# FRDM-Robot-Rev1_9.net
KiCad netlist of a schematic drawn in EAGLE
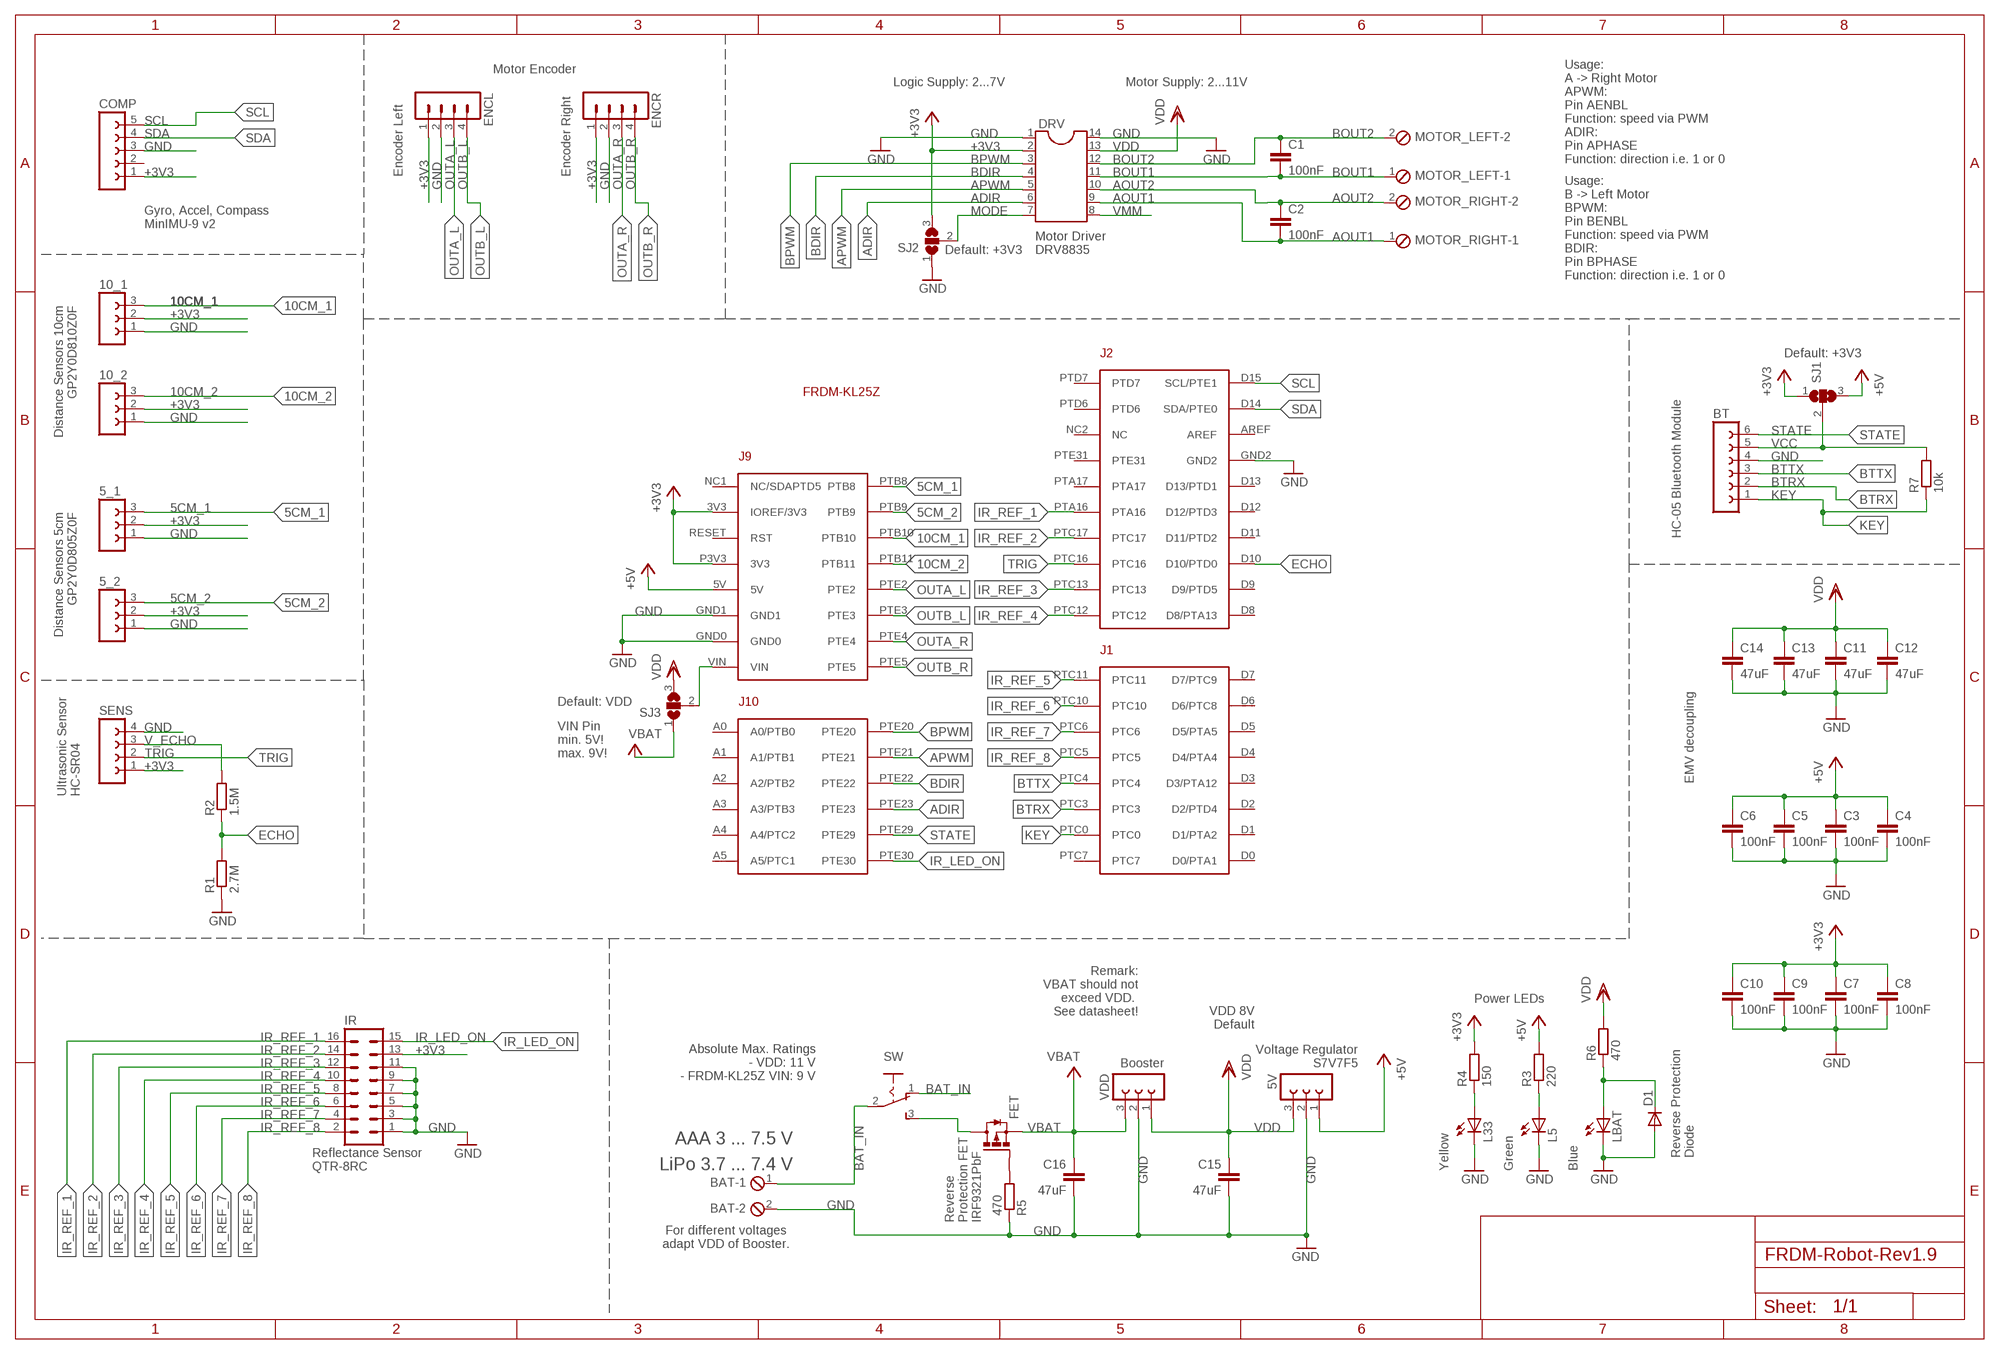
[diagram p0: schematic, sheet 1]

(export (version "E")
  (design (tool "Eeschema 10.0.6"))
  (components
    (comp (ref "5V")
      (value "FE03-1")
      (footprint "eagle-import:FE03-1")
      (libsource (lib "eagle-import") (part "FE03-1"))
    )
    (comp (ref "5_1")
      (value "FE03-1")
      (footprint "eagle-import:FE03-1")
      (libsource (lib "eagle-import") (part "FE03-1"))
    )
    (comp (ref "5_2")
      (value "FE03-1")
      (footprint "eagle-import:FE03-1")
      (libsource (lib "eagle-import") (part "FE03-1"))
    )
    (comp (ref "10_1")
      (value "FE03-1")
      (footprint "eagle-import:FE03-1")
      (libsource (lib "eagle-import") (part "FE03-1"))
    )
    (comp (ref "10_2")
      (value "FE03-1")
      (footprint "eagle-import:FE03-1")
      (libsource (lib "eagle-import") (part "FE03-1"))
    )
    (comp (ref "BAT")
      (value "MPT2")
      (footprint "eagle-import:2POL254")
      (libsource (lib "eagle-import") (part "MPT2"))
    )
    (comp (ref "BT")
      (value "FE06-1")
      (footprint "eagle-import:FE06")
      (libsource (lib "eagle-import") (part "FE06-1"))
    )
    (comp (ref "C1")
      (value "100nF")
      (footprint "eagle-import:C0805")
      (libsource (lib "eagle-import") (part "C-EUC0805"))
    )
    (comp (ref "C2")
      (value "100nF")
      (footprint "eagle-import:C0805")
      (libsource (lib "eagle-import") (part "C-EUC0805"))
    )
    (comp (ref "C3")
      (value "100nF")
      (footprint "eagle-import:C0805")
      (libsource (lib "eagle-import") (part "C-EUC0805"))
    )
    (comp (ref "C4")
      (value "100nF")
      (footprint "eagle-import:C0805")
      (libsource (lib "eagle-import") (part "C-EUC0805"))
    )
    (comp (ref "C5")
      (value "100nF")
      (footprint "eagle-import:C0805")
      (libsource (lib "eagle-import") (part "C-EUC0805"))
    )
    (comp (ref "C6")
      (value "100nF")
      (footprint "eagle-import:C0805")
      (libsource (lib "eagle-import") (part "C-EUC0805"))
    )
    (comp (ref "C7")
      (value "100nF")
      (footprint "eagle-import:C0805")
      (libsource (lib "eagle-import") (part "C-EUC0805"))
    )
    (comp (ref "C8")
      (value "100nF")
      (footprint "eagle-import:C0805")
      (libsource (lib "eagle-import") (part "C-EUC0805"))
    )
    (comp (ref "C9")
      (value "100nF")
      (footprint "eagle-import:C0805")
      (libsource (lib "eagle-import") (part "C-EUC0805"))
    )
    (comp (ref "C10")
      (value "100nF")
      (footprint "eagle-import:C0805")
      (libsource (lib "eagle-import") (part "C-EUC0805"))
    )
    (comp (ref "C11")
      (value "47uF")
      (footprint "eagle-import:C0805")
      (libsource (lib "eagle-import") (part "C-EUC0805"))
    )
    (comp (ref "C12")
      (value "47uF")
      (footprint "eagle-import:C0805")
      (libsource (lib "eagle-import") (part "C-EUC0805"))
    )
    (comp (ref "C13")
      (value "47uF")
      (footprint "eagle-import:C0805")
      (libsource (lib "eagle-import") (part "C-EUC0805"))
    )
    (comp (ref "C14")
      (value "47uF")
      (footprint "eagle-import:C0805")
      (libsource (lib "eagle-import") (part "C-EUC0805"))
    )
    (comp (ref "C15")
      (value "47uF")
      (footprint "eagle-import:C0805")
      (libsource (lib "eagle-import") (part "C-EUC0805"))
    )
    (comp (ref "C16")
      (value "47uF")
      (footprint "eagle-import:C0805")
      (libsource (lib "eagle-import") (part "C-EUC0805"))
    )
    (comp (ref "COMP")
      (value "FE05-1")
      (footprint "eagle-import:FE05-1")
      (libsource (lib "eagle-import") (part "FE05-1"))
    )
    (comp (ref "D1")
      (value "DIODE-SOD123")
      (footprint "eagle-import:SOD123")
      (libsource (lib "eagle-import") (part "DIODE-SOD123"))
    )
    (comp (ref "DRV")
      (value "DIL14")
      (footprint "eagle-import:DIL14")
      (libsource (lib "eagle-import") (part "DIL14"))
    )
    (comp (ref "ENCL")
      (value "MA04-1")
      (footprint "eagle-import:MA04-1")
      (libsource (lib "eagle-import") (part "MA04-1"))
    )
    (comp (ref "ENCR")
      (value "MA04-1")
      (footprint "eagle-import:MA04-1")
      (libsource (lib "eagle-import") (part "MA04-1"))
    )
    (comp (ref "FET")
      (value "P-MOSFET-SO8")
      (footprint "eagle-import:SO-08")
      (libsource (lib "eagle-import") (part "P-MOSFET-SO8"))
    )
    (comp (ref "FRDM1")
      (value "FRDM-KL25ZARDUINO")
      (footprint "eagle-import:FRDM-KL25Z")
      (libsource (lib "eagle-import") (part "FRDM-KL25ZARDUINO"))
    )
    (comp (ref "IR")
      (value "MA08-2")
      (footprint "eagle-import:MA08-2")
      (libsource (lib "eagle-import") (part "MA08-2"))
    )
    (comp (ref "L5")
      (value "LEDCHIP-LED0603")
      (footprint "eagle-import:CHIP-LED0603")
      (libsource (lib "eagle-import") (part "LEDCHIP-LED0603"))
    )
    (comp (ref "L33")
      (value "LEDCHIP-LED0603")
      (footprint "eagle-import:CHIP-LED0603")
      (libsource (lib "eagle-import") (part "LEDCHIP-LED0603"))
    )
    (comp (ref "LBAT")
      (value "LEDCHIP-LED0603")
      (footprint "eagle-import:CHIP-LED0603")
      (libsource (lib "eagle-import") (part "LEDCHIP-LED0603"))
    )
    (comp (ref "MOTOR_LEFT")
      (value "MPT2")
      (footprint "eagle-import:2POL254")
      (libsource (lib "eagle-import") (part "MPT2"))
    )
    (comp (ref "MOTOR_RIGHT")
      (value "MPT2")
      (footprint "eagle-import:2POL254")
      (libsource (lib "eagle-import") (part "MPT2"))
    )
    (comp (ref "R1")
      (value "2.7M")
      (footprint "eagle-import:M0805")
      (libsource (lib "eagle-import") (part "R-EU_M0805"))
    )
    (comp (ref "R2")
      (value "1.5M")
      (footprint "eagle-import:M0805")
      (libsource (lib "eagle-import") (part "R-EU_M0805"))
    )
    (comp (ref "R3")
      (value "220")
      (footprint "eagle-import:M0805")
      (libsource (lib "eagle-import") (part "R-EU_M0805"))
    )
    (comp (ref "R4")
      (value "150")
      (footprint "eagle-import:M0805")
      (libsource (lib "eagle-import") (part "R-EU_M0805"))
    )
    (comp (ref "R5")
      (value "470")
      (footprint "eagle-import:M0805")
      (libsource (lib "eagle-import") (part "R-EU_M0805"))
    )
    (comp (ref "R6")
      (value "470")
      (footprint "eagle-import:M0805")
      (libsource (lib "eagle-import") (part "R-EU_M0805"))
    )
    (comp (ref "R7")
      (value "10k")
      (footprint "eagle-import:M0805")
      (libsource (lib "eagle-import") (part "R-EU_M0805"))
    )
    (comp (ref "SENS")
      (value "FE04-1")
      (footprint "eagle-import:FE04-1")
      (libsource (lib "eagle-import") (part "FE04-1"))
    )
    (comp (ref "SJ1")
      (value "SJ2W")
      (footprint "eagle-import:SJ_2")
      (libsource (lib "eagle-import") (part "SJ2W"))
    )
    (comp (ref "SJ2")
      (value "SJ2W")
      (footprint "eagle-import:SJ_2")
      (libsource (lib "eagle-import") (part "SJ2W"))
    )
    (comp (ref "SJ3")
      (value "SJ2W")
      (footprint "eagle-import:SJ_2")
      (libsource (lib "eagle-import") (part "SJ2W"))
    )
    (comp (ref "SW")
      (value "KNITTER-MFP106D")
      (footprint "eagle-import:KNITTER-MFP106D")
      (libsource (lib "eagle-import") (part "KNITTER-MFP106D"))
    )
    (comp (ref "VDD")
      (value "FE03-1")
      (footprint "eagle-import:FE03-1")
      (libsource (lib "eagle-import") (part "FE03-1"))
    )
  )
  (nets
    (net (code "1") (name "+3V3") (class "Default")
      (node (ref "10_1") (pin "2") (pinfunction "2_2") (pintype "passive"))
      (node (ref "10_2") (pin "2") (pinfunction "2_2") (pintype "passive"))
      (node (ref "5_1") (pin "2") (pinfunction "2_2") (pintype "passive"))
      (node (ref "5_2") (pin "2") (pinfunction "2_2") (pintype "passive"))
      (node (ref "C10") (pin "1") (pinfunction "1_1") (pintype "passive"))
      (node (ref "C7") (pin "1") (pinfunction "1_1") (pintype "passive"))
      (node (ref "C8") (pin "1") (pinfunction "1_1") (pintype "passive"))
      (node (ref "C9") (pin "1") (pinfunction "1_1") (pintype "passive"))
      (node (ref "COMP") (pin "1") (pinfunction "1_1") (pintype "passive"))
      (node (ref "DRV") (pin "2") (pinfunction "2_2") (pintype "passive"))
      (node (ref "ENCL") (pin "1") (pinfunction "1_1") (pintype "passive"))
      (node (ref "ENCR") (pin "1") (pinfunction "1_1") (pintype "passive"))
      (node (ref "FRDM1") (pin "3V3") (pinfunction "IOREF/3V3_3V3") (pintype "bidirectional"))
      (node (ref "FRDM1") (pin "P3V3") (pinfunction "3V3_P3V3") (pintype "bidirectional"))
      (node (ref "IR") (pin "13") (pinfunction "13_13") (pintype "passive"))
      (node (ref "R4") (pin "2") (pinfunction "2_2") (pintype "passive"))
      (node (ref "SENS") (pin "1") (pinfunction "1_1") (pintype "passive"))
      (node (ref "SJ1") (pin "1") (pinfunction "1_1") (pintype "passive"))
      (node (ref "SJ2") (pin "3") (pinfunction "3_3") (pintype "passive"))
    )
    (net (code "2") (name "+5V") (class "Default")
      (node (ref "5V") (pin "1") (pinfunction "1_1") (pintype "passive"))
      (node (ref "C3") (pin "1") (pinfunction "1_1") (pintype "passive"))
      (node (ref "C4") (pin "1") (pinfunction "1_1") (pintype "passive"))
      (node (ref "C5") (pin "1") (pinfunction "1_1") (pintype "passive"))
      (node (ref "C6") (pin "1") (pinfunction "1_1") (pintype "passive"))
      (node (ref "FRDM1") (pin "5V") (pinfunction "5V_5V") (pintype "bidirectional"))
      (node (ref "R3") (pin "2") (pinfunction "2_2") (pintype "passive"))
      (node (ref "SJ1") (pin "3") (pinfunction "3_3") (pintype "passive"))
    )
    (net (code "3") (name "/AOUT1") (class "Default")
      (node (ref "C2") (pin "2") (pinfunction "2_2") (pintype "passive"))
      (node (ref "DRV") (pin "9") (pinfunction "9_9") (pintype "passive"))
      (node (ref "MOTOR_RIGHT") (pin "1") (pinfunction "1_1") (pintype "passive"))
    )
    (net (code "4") (name "/AOUT2") (class "Default")
      (node (ref "C2") (pin "1") (pinfunction "1_1") (pintype "passive"))
      (node (ref "DRV") (pin "10") (pinfunction "10_10") (pintype "passive"))
      (node (ref "MOTOR_RIGHT") (pin "2") (pinfunction "1_2") (pintype "passive"))
    )
    (net (code "5") (name "/BAT_IN") (class "Default")
      (node (ref "BAT") (pin "1") (pinfunction "1_1") (pintype "passive"))
      (node (ref "SW") (pin "1") (pinfunction "O_1") (pintype "passive"))
      (node (ref "SW") (pin "2") (pinfunction "P_2") (pintype "passive"))
    )
    (net (code "6") (name "/BOUT1") (class "Default")
      (node (ref "C1") (pin "2") (pinfunction "2_2") (pintype "passive"))
      (node (ref "DRV") (pin "11") (pinfunction "11_11") (pintype "passive"))
      (node (ref "MOTOR_LEFT") (pin "1") (pinfunction "1_1") (pintype "passive"))
    )
    (net (code "7") (name "/BOUT2") (class "Default")
      (node (ref "C1") (pin "1") (pinfunction "1_1") (pintype "passive"))
      (node (ref "DRV") (pin "12") (pinfunction "12_12") (pintype "passive"))
      (node (ref "MOTOR_LEFT") (pin "2") (pinfunction "1_2") (pintype "passive"))
    )
    (net (code "8") (name "/MODE") (class "Default")
      (node (ref "DRV") (pin "7") (pinfunction "7_7") (pintype "passive"))
      (node (ref "SJ2") (pin "2") (pinfunction "2_2") (pintype "passive"))
    )
    (net (code "9") (name "/VCC") (class "Default")
      (node (ref "BT") (pin "5") (pinfunction "5_5") (pintype "passive"))
      (node (ref "R7") (pin "2") (pinfunction "2_2") (pintype "passive"))
      (node (ref "SJ1") (pin "2") (pinfunction "2_2") (pintype "passive"))
    )
    (net (code "10") (name "/VMM") (class "Default")
      (node (ref "DRV") (pin "8") (pinfunction "8_8") (pintype "passive"))
    )
    (net (code "11") (name "/V_ECHO") (class "Default")
      (node (ref "R2") (pin "2") (pinfunction "2_2") (pintype "passive"))
      (node (ref "SENS") (pin "3") (pinfunction "3_3") (pintype "passive"))
    )
    (net (code "12") (name "5CM_1") (class "Default")
      (node (ref "5_1") (pin "3") (pinfunction "3_3") (pintype "passive"))
      (node (ref "FRDM1") (pin "PTB8") (pinfunction "PTB8_PTB8") (pintype "bidirectional"))
    )
    (net (code "13") (name "5CM_2") (class "Default")
      (node (ref "5_2") (pin "3") (pinfunction "3_3") (pintype "passive"))
      (node (ref "FRDM1") (pin "PTB9") (pinfunction "PTB9_PTB9") (pintype "bidirectional"))
    )
    (net (code "14") (name "10CM_1") (class "Default")
      (node (ref "10_1") (pin "3") (pinfunction "3_3") (pintype "passive"))
      (node (ref "FRDM1") (pin "PTB10") (pinfunction "PTB10_PTB10") (pintype "bidirectional"))
    )
    (net (code "15") (name "10CM_2") (class "Default")
      (node (ref "10_2") (pin "3") (pinfunction "3_3") (pintype "passive"))
      (node (ref "FRDM1") (pin "PTB11") (pinfunction "PTB11_PTB11") (pintype "bidirectional"))
    )
    (net (code "16") (name "ADIR") (class "Default")
      (node (ref "DRV") (pin "6") (pinfunction "6_6") (pintype "passive"))
      (node (ref "FRDM1") (pin "PTE23") (pinfunction "PTE23_PTE23") (pintype "bidirectional"))
    )
    (net (code "17") (name "APWM") (class "Default")
      (node (ref "DRV") (pin "5") (pinfunction "5_5") (pintype "passive"))
      (node (ref "FRDM1") (pin "PTE21") (pinfunction "PTE21_PTE21") (pintype "bidirectional"))
    )
    (net (code "18") (name "BDIR") (class "Default")
      (node (ref "DRV") (pin "4") (pinfunction "4_4") (pintype "passive"))
      (node (ref "FRDM1") (pin "PTE22") (pinfunction "PTE22_PTE22") (pintype "bidirectional"))
    )
    (net (code "19") (name "BPWM") (class "Default")
      (node (ref "DRV") (pin "3") (pinfunction "3_3") (pintype "passive"))
      (node (ref "FRDM1") (pin "PTE20") (pinfunction "PTE20_PTE20") (pintype "bidirectional"))
    )
    (net (code "20") (name "BTRX") (class "Default")
      (node (ref "BT") (pin "2") (pinfunction "2_2") (pintype "passive"))
      (node (ref "FRDM1") (pin "PTC3") (pinfunction "PTC3_PTC3") (pintype "bidirectional"))
    )
    (net (code "21") (name "BTTX") (class "Default")
      (node (ref "BT") (pin "3") (pinfunction "3_3") (pintype "passive"))
      (node (ref "FRDM1") (pin "PTC4") (pinfunction "PTC4_PTC4") (pintype "bidirectional"))
    )
    (net (code "22") (name "ECHO") (class "Default")
      (node (ref "FRDM1") (pin "D10") (pinfunction "D10/PTD0_D10") (pintype "bidirectional"))
      (node (ref "R1") (pin "2") (pinfunction "2_2") (pintype "passive"))
      (node (ref "R2") (pin "1") (pinfunction "1_1") (pintype "passive"))
    )
    (net (code "23") (name "GND") (class "Default")
      (node (ref "10_1") (pin "1") (pinfunction "1_1") (pintype "passive"))
      (node (ref "10_2") (pin "1") (pinfunction "1_1") (pintype "passive"))
      (node (ref "5V") (pin "2") (pinfunction "2_2") (pintype "passive"))
      (node (ref "5_1") (pin "1") (pinfunction "1_1") (pintype "passive"))
      (node (ref "5_2") (pin "1") (pinfunction "1_1") (pintype "passive"))
      (node (ref "BAT") (pin "2") (pinfunction "1_2") (pintype "passive"))
      (node (ref "BT") (pin "4") (pinfunction "4_4") (pintype "passive"))
      (node (ref "C10") (pin "2") (pinfunction "2_2") (pintype "passive"))
      (node (ref "C11") (pin "2") (pinfunction "2_2") (pintype "passive"))
      (node (ref "C12") (pin "2") (pinfunction "2_2") (pintype "passive"))
      (node (ref "C13") (pin "2") (pinfunction "2_2") (pintype "passive"))
      (node (ref "C14") (pin "2") (pinfunction "2_2") (pintype "passive"))
      (node (ref "C15") (pin "2") (pinfunction "2_2") (pintype "passive"))
      (node (ref "C16") (pin "2") (pinfunction "2_2") (pintype "passive"))
      (node (ref "C3") (pin "2") (pinfunction "2_2") (pintype "passive"))
      (node (ref "C4") (pin "2") (pinfunction "2_2") (pintype "passive"))
      (node (ref "C5") (pin "2") (pinfunction "2_2") (pintype "passive"))
      (node (ref "C6") (pin "2") (pinfunction "2_2") (pintype "passive"))
      (node (ref "C7") (pin "2") (pinfunction "2_2") (pintype "passive"))
      (node (ref "C8") (pin "2") (pinfunction "2_2") (pintype "passive"))
      (node (ref "C9") (pin "2") (pinfunction "2_2") (pintype "passive"))
      (node (ref "COMP") (pin "3") (pinfunction "3_3") (pintype "passive"))
      (node (ref "D1") (pin "A") (pinfunction "A_A") (pintype "passive"))
      (node (ref "DRV") (pin "1") (pinfunction "1_1") (pintype "passive"))
      (node (ref "DRV") (pin "14") (pinfunction "14_14") (pintype "passive"))
      (node (ref "ENCL") (pin "2") (pinfunction "2_2") (pintype "passive"))
      (node (ref "ENCR") (pin "2") (pinfunction "2_2") (pintype "passive"))
      (node (ref "FRDM1") (pin "GND0") (pinfunction "GND0_GND0") (pintype "bidirectional"))
      (node (ref "FRDM1") (pin "GND1") (pinfunction "GND1_GND1") (pintype "bidirectional"))
      (node (ref "FRDM1") (pin "GND2") (pinfunction "GND2_GND2") (pintype "bidirectional"))
      (node (ref "IR") (pin "1") (pinfunction "1_1") (pintype "passive"))
      (node (ref "IR") (pin "11") (pinfunction "11_11") (pintype "passive"))
      (node (ref "IR") (pin "3") (pinfunction "3_3") (pintype "passive"))
      (node (ref "IR") (pin "5") (pinfunction "5_5") (pintype "passive"))
      (node (ref "IR") (pin "7") (pinfunction "7_7") (pintype "passive"))
      (node (ref "IR") (pin "9") (pinfunction "9_9") (pintype "passive"))
      (node (ref "L33") (pin "C") (pinfunction "C_C") (pintype "passive"))
      (node (ref "L5") (pin "C") (pinfunction "C_C") (pintype "passive"))
      (node (ref "LBAT") (pin "C") (pinfunction "C_C") (pintype "passive"))
      (node (ref "R1") (pin "1") (pinfunction "1_1") (pintype "passive"))
      (node (ref "R5") (pin "1") (pinfunction "1_1") (pintype "passive"))
      (node (ref "SENS") (pin "4") (pinfunction "4_4") (pintype "passive"))
      (node (ref "SJ2") (pin "1") (pinfunction "1_1") (pintype "passive"))
      (node (ref "VDD") (pin "2") (pinfunction "2_2") (pintype "passive"))
    )
    (net (code "24") (name "IR_LED_ON") (class "Default")
      (node (ref "FRDM1") (pin "PTE30") (pinfunction "PTE30_PTE30") (pintype "bidirectional"))
      (node (ref "IR") (pin "15") (pinfunction "15_15") (pintype "passive"))
    )
    (net (code "25") (name "IR_REF_1") (class "Default")
      (node (ref "FRDM1") (pin "PTA16") (pinfunction "PTA16_PTA16") (pintype "bidirectional"))
      (node (ref "IR") (pin "16") (pinfunction "16_16") (pintype "passive"))
    )
    (net (code "26") (name "IR_REF_2") (class "Default")
      (node (ref "FRDM1") (pin "PTC17") (pinfunction "PTC17_PTC17") (pintype "bidirectional"))
      (node (ref "IR") (pin "14") (pinfunction "14_14") (pintype "passive"))
    )
    (net (code "27") (name "IR_REF_3") (class "Default")
      (node (ref "FRDM1") (pin "PTC13") (pinfunction "PTC13_PTC13") (pintype "bidirectional"))
      (node (ref "IR") (pin "12") (pinfunction "12_12") (pintype "passive"))
    )
    (net (code "28") (name "IR_REF_4") (class "Default")
      (node (ref "FRDM1") (pin "PTC12") (pinfunction "PTC12_PTC12") (pintype "bidirectional"))
      (node (ref "IR") (pin "10") (pinfunction "10_10") (pintype "passive"))
    )
    (net (code "29") (name "IR_REF_5") (class "Default")
      (node (ref "FRDM1") (pin "PTC11") (pinfunction "PTC11_PTC11") (pintype "bidirectional"))
      (node (ref "IR") (pin "8") (pinfunction "8_8") (pintype "passive"))
    )
    (net (code "30") (name "IR_REF_6") (class "Default")
      (node (ref "FRDM1") (pin "PTC10") (pinfunction "PTC10_PTC10") (pintype "bidirectional"))
      (node (ref "IR") (pin "6") (pinfunction "6_6") (pintype "passive"))
    )
    (net (code "31") (name "IR_REF_7") (class "Default")
      (node (ref "FRDM1") (pin "PTC6") (pinfunction "PTC6_PTC6") (pintype "bidirectional"))
      (node (ref "IR") (pin "4") (pinfunction "4_4") (pintype "passive"))
    )
    (net (code "32") (name "IR_REF_8") (class "Default")
      (node (ref "FRDM1") (pin "PTC5") (pinfunction "PTC5_PTC5") (pintype "bidirectional"))
      (node (ref "IR") (pin "2") (pinfunction "2_2") (pintype "passive"))
    )
    (net (code "33") (name "KEY") (class "Default")
      (node (ref "BT") (pin "1") (pinfunction "1_1") (pintype "passive"))
      (node (ref "FRDM1") (pin "PTC0") (pinfunction "PTC0_PTC0") (pintype "bidirectional"))
      (node (ref "R7") (pin "1") (pinfunction "1_1") (pintype "passive"))
    )
    (net (code "34") (name "Net-(D1-PadC)") (class "Default")
      (node (ref "D1") (pin "C") (pinfunction "C_C") (pintype "passive"))
      (node (ref "LBAT") (pin "A") (pinfunction "A_A") (pintype "passive"))
      (node (ref "R6") (pin "1") (pinfunction "1_1") (pintype "passive"))
    )
    (net (code "35") (name "Net-(FET-G)") (class "Default")
      (node (ref "FET") (pin "4") (pinfunction "G_4") (pintype "passive"))
      (node (ref "R5") (pin "2") (pinfunction "2_2") (pintype "passive"))
    )
    (net (code "36") (name "Net-(FRDM1-PadVIN)") (class "Default")
      (node (ref "FRDM1") (pin "VIN") (pinfunction "VIN_VIN") (pintype "bidirectional"))
      (node (ref "SJ3") (pin "2") (pinfunction "2_2") (pintype "passive"))
    )
    (net (code "37") (name "Net-(L5-PadA)") (class "Default")
      (node (ref "L5") (pin "A") (pinfunction "A_A") (pintype "passive"))
      (node (ref "R3") (pin "1") (pinfunction "1_1") (pintype "passive"))
    )
    (net (code "38") (name "Net-(L33-PadA)") (class "Default")
      (node (ref "L33") (pin "A") (pinfunction "A_A") (pintype "passive"))
      (node (ref "R4") (pin "1") (pinfunction "1_1") (pintype "passive"))
    )
    (net (code "39") (name "Net-(SW-S)") (class "Default")
      (node (ref "FET") (pin "5") (pinfunction "D_5") (pintype "passive"))
      (node (ref "FET") (pin "6") (pinfunction "D_6") (pintype "passive"))
      (node (ref "FET") (pin "7") (pinfunction "D_7") (pintype "passive"))
      (node (ref "FET") (pin "8") (pinfunction "D_8") (pintype "passive"))
      (node (ref "SW") (pin "3") (pinfunction "S_3") (pintype "passive"))
    )
    (net (code "40") (name "OUTA_L") (class "Default")
      (node (ref "ENCL") (pin "3") (pinfunction "3_3") (pintype "passive"))
      (node (ref "FRDM1") (pin "PTE2") (pinfunction "PTE2_PTE2") (pintype "bidirectional"))
    )
    (net (code "41") (name "OUTA_R") (class "Default")
      (node (ref "ENCR") (pin "3") (pinfunction "3_3") (pintype "passive"))
      (node (ref "FRDM1") (pin "PTE4") (pinfunction "PTE4_PTE4") (pintype "bidirectional"))
    )
    (net (code "42") (name "OUTB_L") (class "Default")
      (node (ref "ENCL") (pin "4") (pinfunction "4_4") (pintype "passive"))
      (node (ref "FRDM1") (pin "PTE3") (pinfunction "PTE3_PTE3") (pintype "bidirectional"))
    )
    (net (code "43") (name "OUTB_R") (class "Default")
      (node (ref "ENCR") (pin "4") (pinfunction "4_4") (pintype "passive"))
      (node (ref "FRDM1") (pin "PTE5") (pinfunction "PTE5_PTE5") (pintype "bidirectional"))
    )
    (net (code "44") (name "SCL") (class "Default")
      (node (ref "COMP") (pin "5") (pinfunction "5_5") (pintype "passive"))
      (node (ref "FRDM1") (pin "D15") (pinfunction "SCL/PTE1_D15") (pintype "bidirectional"))
    )
    (net (code "45") (name "SDA") (class "Default")
      (node (ref "COMP") (pin "4") (pinfunction "4_4") (pintype "passive"))
      (node (ref "FRDM1") (pin "D14") (pinfunction "SDA/PTE0_D14") (pintype "bidirectional"))
    )
    (net (code "46") (name "STATE") (class "Default")
      (node (ref "BT") (pin "6") (pinfunction "6_6") (pintype "passive"))
      (node (ref "FRDM1") (pin "PTE29") (pinfunction "PTE29_PTE29") (pintype "bidirectional"))
    )
    (net (code "47") (name "TRIG") (class "Default")
      (node (ref "FRDM1") (pin "PTC16") (pinfunction "PTC16_PTC16") (pintype "bidirectional"))
      (node (ref "SENS") (pin "2") (pinfunction "2_2") (pintype "passive"))
    )
    (net (code "48") (name "VBAT") (class "Default")
      (node (ref "C16") (pin "1") (pinfunction "1_1") (pintype "passive"))
      (node (ref "FET") (pin "1") (pinfunction "S_1") (pintype "passive"))
      (node (ref "FET") (pin "2") (pinfunction "S_2") (pintype "passive"))
      (node (ref "FET") (pin "3") (pinfunction "S_3") (pintype "passive"))
      (node (ref "SJ3") (pin "1") (pinfunction "1_1") (pintype "passive"))
      (node (ref "VDD") (pin "3") (pinfunction "3_3") (pintype "passive"))
    )
    (net (code "49") (name "VDD") (class "Default")
      (node (ref "5V") (pin "3") (pinfunction "3_3") (pintype "passive"))
      (node (ref "C11") (pin "1") (pinfunction "1_1") (pintype "passive"))
      (node (ref "C12") (pin "1") (pinfunction "1_1") (pintype "passive"))
      (node (ref "C13") (pin "1") (pinfunction "1_1") (pintype "passive"))
      (node (ref "C14") (pin "1") (pinfunction "1_1") (pintype "passive"))
      (node (ref "C15") (pin "1") (pinfunction "1_1") (pintype "passive"))
      (node (ref "DRV") (pin "13") (pinfunction "13_13") (pintype "passive"))
      (node (ref "R6") (pin "2") (pinfunction "2_2") (pintype "passive"))
      (node (ref "SJ3") (pin "3") (pinfunction "3_3") (pintype "passive"))
      (node (ref "VDD") (pin "1") (pinfunction "1_1") (pintype "passive"))
    )
    (net (code "50") (name "unconnected-(COMP-Pad2)") (class "Default")
      (node (ref "COMP") (pin "2") (pinfunction "2_2") (pintype "passive"))
    )
    (net (code "51") (name "unconnected-(FRDM1-A0{slash}PTB0-PadA0)") (class "Default")
      (node (ref "FRDM1") (pin "A0") (pinfunction "A0/PTB0_A0") (pintype "bidirectional"))
    )
    (net (code "52") (name "unconnected-(FRDM1-A1{slash}PTB1-PadA1)") (class "Default")
      (node (ref "FRDM1") (pin "A1") (pinfunction "A1/PTB1_A1") (pintype "bidirectional"))
    )
    (net (code "53") (name "unconnected-(FRDM1-A2{slash}PTB2-PadA2)") (class "Default")
      (node (ref "FRDM1") (pin "A2") (pinfunction "A2/PTB2_A2") (pintype "bidirectional"))
    )
    (net (code "54") (name "unconnected-(FRDM1-A3{slash}PTB3-PadA3)") (class "Default")
      (node (ref "FRDM1") (pin "A3") (pinfunction "A3/PTB3_A3") (pintype "bidirectional"))
    )
    (net (code "55") (name "unconnected-(FRDM1-A4{slash}PTC2-PadA4)") (class "Default")
      (node (ref "FRDM1") (pin "A4") (pinfunction "A4/PTC2_A4") (pintype "bidirectional"))
    )
    (net (code "56") (name "unconnected-(FRDM1-A5{slash}PTC1-PadA5)") (class "Default")
      (node (ref "FRDM1") (pin "A5") (pinfunction "A5/PTC1_A5") (pintype "bidirectional"))
    )
    (net (code "57") (name "unconnected-(FRDM1-D0{slash}PTA1-PadD0)") (class "Default")
      (node (ref "FRDM1") (pin "D0") (pinfunction "D0/PTA1_D0") (pintype "bidirectional"))
    )
    (net (code "58") (name "unconnected-(FRDM1-D1{slash}PTA2-PadD1)") (class "Default")
      (node (ref "FRDM1") (pin "D1") (pinfunction "D1/PTA2_D1") (pintype "bidirectional"))
    )
    (net (code "59") (name "unconnected-(FRDM1-D2{slash}PTD4-PadD2)") (class "Default")
      (node (ref "FRDM1") (pin "D2") (pinfunction "D2/PTD4_D2") (pintype "bidirectional"))
    )
    (net (code "60") (name "unconnected-(FRDM1-D3{slash}PTA12-PadD3)") (class "Default")
      (node (ref "FRDM1") (pin "D3") (pinfunction "D3/PTA12_D3") (pintype "bidirectional"))
    )
    (net (code "61") (name "unconnected-(FRDM1-D4{slash}PTA4-PadD4)") (class "Default")
      (node (ref "FRDM1") (pin "D4") (pinfunction "D4/PTA4_D4") (pintype "bidirectional"))
    )
    (net (code "62") (name "unconnected-(FRDM1-D5{slash}PTA5-PadD5)") (class "Default")
      (node (ref "FRDM1") (pin "D5") (pinfunction "D5/PTA5_D5") (pintype "bidirectional"))
    )
    (net (code "63") (name "unconnected-(FRDM1-D6{slash}PTC8-PadD6)") (class "Default")
      (node (ref "FRDM1") (pin "D6") (pinfunction "D6/PTC8_D6") (pintype "bidirectional"))
    )
    (net (code "64") (name "unconnected-(FRDM1-D7{slash}PTC9-PadD7)") (class "Default")
      (node (ref "FRDM1") (pin "D7") (pinfunction "D7/PTC9_D7") (pintype "bidirectional"))
    )
    (net (code "65") (name "unconnected-(FRDM1-D8{slash}PTA13-PadD8)") (class "Default")
      (node (ref "FRDM1") (pin "D8") (pinfunction "D8/PTA13_D8") (pintype "bidirectional"))
    )
    (net (code "66") (name "unconnected-(FRDM1-D9{slash}PTD5-PadD9)") (class "Default")
      (node (ref "FRDM1") (pin "D9") (pinfunction "D9/PTD5_D9") (pintype "bidirectional"))
    )
    (net (code "67") (name "unconnected-(FRDM1-D11{slash}PTD2-PadD11)") (class "Default")
      (node (ref "FRDM1") (pin "D11") (pinfunction "D11/PTD2_D11") (pintype "bidirectional"))
    )
    (net (code "68") (name "unconnected-(FRDM1-D12{slash}PTD3-PadD12)") (class "Default")
      (node (ref "FRDM1") (pin "D12") (pinfunction "D12/PTD3_D12") (pintype "bidirectional"))
    )
    (net (code "69") (name "unconnected-(FRDM1-D13{slash}PTD1-PadD13)") (class "Default")
      (node (ref "FRDM1") (pin "D13") (pinfunction "D13/PTD1_D13") (pintype "bidirectional"))
    )
    (net (code "70") (name "unconnected-(FRDM1-NC-PadNC2)") (class "Default")
      (node (ref "FRDM1") (pin "NC2") (pinfunction "NC_NC2") (pintype "bidirectional"))
    )
    (net (code "71") (name "unconnected-(FRDM1-NC{slash}SDAPTD5-PadNC1)") (class "Default")
      (node (ref "FRDM1") (pin "NC1") (pinfunction "NC/SDAPTD5_NC1") (pintype "bidirectional"))
    )
    (net (code "72") (name "unconnected-(FRDM1-PadAREF)") (class "Default")
      (node (ref "FRDM1") (pin "AREF") (pinfunction "AREF_AREF") (pintype "bidirectional"))
    )
    (net (code "73") (name "unconnected-(FRDM1-PadPTA17)") (class "Default")
      (node (ref "FRDM1") (pin "PTA17") (pinfunction "PTA17_PTA17") (pintype "bidirectional"))
    )
    (net (code "74") (name "unconnected-(FRDM1-PadPTC7)") (class "Default")
      (node (ref "FRDM1") (pin "PTC7") (pinfunction "PTC7_PTC7") (pintype "bidirectional"))
    )
    (net (code "75") (name "unconnected-(FRDM1-PadPTD6)") (class "Default")
      (node (ref "FRDM1") (pin "PTD6") (pinfunction "PTD6_PTD6") (pintype "bidirectional"))
    )
    (net (code "76") (name "unconnected-(FRDM1-PadPTD7)") (class "Default")
      (node (ref "FRDM1") (pin "PTD7") (pinfunction "PTD7_PTD7") (pintype "bidirectional"))
    )
    (net (code "77") (name "unconnected-(FRDM1-PadPTE31)") (class "Default")
      (node (ref "FRDM1") (pin "PTE31") (pinfunction "PTE31_PTE31") (pintype "bidirectional"))
    )
    (net (code "78") (name "unconnected-(FRDM1-RST-PadRESET)") (class "Default")
      (node (ref "FRDM1") (pin "RESET") (pinfunction "RST_RESET") (pintype "bidirectional"))
    )
  )
)
